# Display_Module.net
KiCad netlist of a schematic drawn in Altium Designer
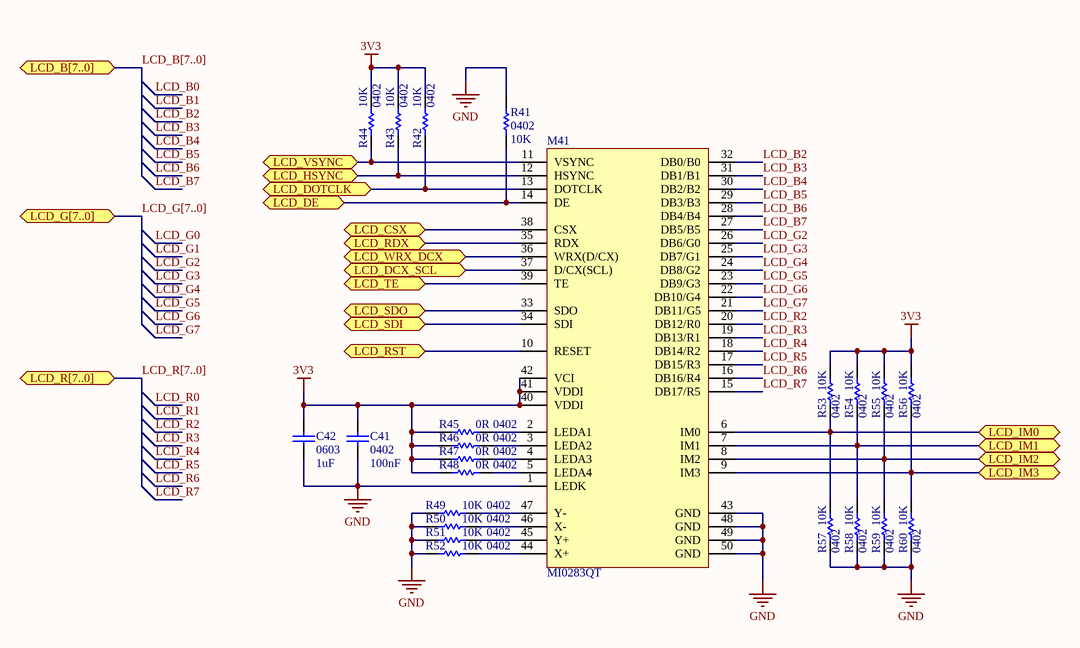
[diagram p0: Display Module.SchDoc]

(export (version "E")
  (design (tool "Eeschema 10.0.6"))
  (components
    (comp (ref "C41")
      (value "0402")
      (footprint "CAPC1005X06N")
      (description "Capacitor")
      (fields (field (name "ALTIUM_VALUE") "100nF") (field (name "PUBLISHER") "Altium Limited"))
      (libsource (lib "Miscellaneous Devices") (part "Cap"))
    )
    (comp (ref "C42")
      (value "0603")
      (footprint "CAPC1608X10N")
      (description "Capacitor")
      (fields (field (name "ALTIUM_VALUE") "1uF") (field (name "PUBLISHER") "Altium Limited"))
      (libsource (lib "Miscellaneous Devices") (part "Cap"))
    )
    (comp (ref "M41")
      (value "MI0283QT")
      (footprint "2.8_SCREEN_MODULE_SKT")
      (libsource (lib "Schematic_Modules_NES") (part "Screen Module"))
    )
    (comp (ref "R41")
      (value "0402")
      (footprint "RESC1005X04N")
      (description "Resistor")
      (fields (field (name "ALTIUM_VALUE") "10K") (field (name "PUBLISHER") "Altium Limited"))
      (libsource (lib "Miscellaneous Devices") (part "Res1"))
    )
    (comp (ref "R42")
      (value "0402")
      (footprint "RESC1005X04N")
      (description "Resistor")
      (fields (field (name "ALTIUM_VALUE") "10K") (field (name "PUBLISHER") "Altium Limited"))
      (libsource (lib "Miscellaneous Devices") (part "Res1"))
    )
    (comp (ref "R43")
      (value "0402")
      (footprint "RESC1005X04N")
      (description "Resistor")
      (fields (field (name "ALTIUM_VALUE") "10K") (field (name "PUBLISHER") "Altium Limited"))
      (libsource (lib "Miscellaneous Devices") (part "Res1"))
    )
    (comp (ref "R44")
      (value "0402")
      (footprint "RESC1005X04N")
      (description "Resistor")
      (fields (field (name "ALTIUM_VALUE") "10K") (field (name "PUBLISHER") "Altium Limited"))
      (libsource (lib "Miscellaneous Devices") (part "Res1"))
    )
    (comp (ref "R45")
      (value "0402")
      (footprint "RESC1005X04N")
      (description "Resistor")
      (fields (field (name "ALTIUM_VALUE") "0R") (field (name "PUBLISHER") "Altium Limited"))
      (libsource (lib "Miscellaneous Devices") (part "Res1"))
    )
    (comp (ref "R46")
      (value "0402")
      (footprint "RESC1005X04N")
      (description "Resistor")
      (fields (field (name "ALTIUM_VALUE") "0R") (field (name "PUBLISHER") "Altium Limited"))
      (libsource (lib "Miscellaneous Devices") (part "Res1"))
    )
    (comp (ref "R47")
      (value "0402")
      (footprint "RESC1005X04N")
      (description "Resistor")
      (fields (field (name "ALTIUM_VALUE") "0R") (field (name "PUBLISHER") "Altium Limited"))
      (libsource (lib "Miscellaneous Devices") (part "Res1"))
    )
    (comp (ref "R48")
      (value "0402")
      (footprint "RESC1005X04N")
      (description "Resistor")
      (fields (field (name "ALTIUM_VALUE") "0R") (field (name "PUBLISHER") "Altium Limited"))
      (libsource (lib "Miscellaneous Devices") (part "Res1"))
    )
    (comp (ref "R49")
      (value "0402")
      (footprint "RESC1005X04N")
      (description "Resistor")
      (fields (field (name "ALTIUM_VALUE") "10K") (field (name "PUBLISHER") "Altium Limited"))
      (libsource (lib "Miscellaneous Devices") (part "Res1"))
    )
    (comp (ref "R50")
      (value "0402")
      (footprint "RESC1005X04N")
      (description "Resistor")
      (fields (field (name "ALTIUM_VALUE") "10K") (field (name "PUBLISHER") "Altium Limited"))
      (libsource (lib "Miscellaneous Devices") (part "Res1"))
    )
    (comp (ref "R51")
      (value "0402")
      (footprint "RESC1005X04N")
      (description "Resistor")
      (fields (field (name "ALTIUM_VALUE") "10K") (field (name "PUBLISHER") "Altium Limited"))
      (libsource (lib "Miscellaneous Devices") (part "Res1"))
    )
    (comp (ref "R52")
      (value "0402")
      (footprint "RESC1005X04N")
      (description "Resistor")
      (fields (field (name "ALTIUM_VALUE") "10K") (field (name "PUBLISHER") "Altium Limited"))
      (libsource (lib "Miscellaneous Devices") (part "Res1"))
    )
    (comp (ref "R53")
      (value "0402")
      (footprint "RESC1005X04N")
      (description "Resistor")
      (fields (field (name "ALTIUM_VALUE") "10K") (field (name "PUBLISHER") "Altium Limited"))
      (libsource (lib "Miscellaneous Devices") (part "Res1"))
    )
    (comp (ref "R54")
      (value "0402")
      (footprint "RESC1005X04N")
      (description "Resistor")
      (fields (field (name "ALTIUM_VALUE") "10K") (field (name "PUBLISHER") "Altium Limited"))
      (libsource (lib "Miscellaneous Devices") (part "Res1"))
    )
    (comp (ref "R55")
      (value "0402")
      (footprint "RESC1005X04N")
      (description "Resistor")
      (fields (field (name "ALTIUM_VALUE") "10K") (field (name "PUBLISHER") "Altium Limited"))
      (libsource (lib "Miscellaneous Devices") (part "Res1"))
    )
    (comp (ref "R56")
      (value "0402")
      (footprint "RESC1005X04N")
      (description "Resistor")
      (fields (field (name "ALTIUM_VALUE") "10K") (field (name "PUBLISHER") "Altium Limited"))
      (libsource (lib "Miscellaneous Devices") (part "Res1"))
    )
    (comp (ref "R57")
      (value "0402")
      (footprint "RESC1005X04N")
      (description "Resistor")
      (fields (field (name "ALTIUM_VALUE") "10K") (field (name "PUBLISHER") "Altium Limited"))
      (libsource (lib "Miscellaneous Devices") (part "Res1"))
    )
    (comp (ref "R58")
      (value "0402")
      (footprint "RESC1005X04N")
      (description "Resistor")
      (fields (field (name "ALTIUM_VALUE") "10K") (field (name "PUBLISHER") "Altium Limited"))
      (libsource (lib "Miscellaneous Devices") (part "Res1"))
    )
    (comp (ref "R59")
      (value "0402")
      (footprint "RESC1005X04N")
      (description "Resistor")
      (fields (field (name "ALTIUM_VALUE") "10K") (field (name "PUBLISHER") "Altium Limited"))
      (libsource (lib "Miscellaneous Devices") (part "Res1"))
    )
    (comp (ref "R60")
      (value "0402")
      (footprint "RESC1005X04N")
      (description "Resistor")
      (fields (field (name "ALTIUM_VALUE") "10K") (field (name "PUBLISHER") "Altium Limited"))
      (libsource (lib "Miscellaneous Devices") (part "Res1"))
    )
  )
  (nets
    (net (code "3") (name "/LCD_B2") (class "Default")
      (node (ref "M41") (pin "32") (pinfunction "DB0/B0_32") (pintype "passive"))
    )
    (net (code "4") (name "/LCD_B3") (class "Default")
      (node (ref "M41") (pin "31") (pinfunction "DB1/B1_31") (pintype "passive"))
    )
    (net (code "5") (name "/LCD_B4") (class "Default")
      (node (ref "M41") (pin "30") (pinfunction "DB2/B2_30") (pintype "passive"))
    )
    (net (code "6") (name "/LCD_B5") (class "Default")
      (node (ref "M41") (pin "29") (pinfunction "DB3/B3_29") (pintype "passive"))
    )
    (net (code "7") (name "/LCD_B6") (class "Default")
      (node (ref "M41") (pin "28") (pinfunction "DB4/B4_28") (pintype "passive"))
    )
    (net (code "8") (name "/LCD_B7") (class "Default")
      (node (ref "M41") (pin "27") (pinfunction "DB5/B5_27") (pintype "passive"))
    )
    (net (code "10") (name "/LCD_CSX") (class "Default")
      (node (ref "M41") (pin "38") (pinfunction "CSX_38") (pintype "passive"))
    )
    (net (code "11") (name "/LCD_DCX_SCL") (class "Default")
      (node (ref "M41") (pin "37") (pinfunction "D/CX(SCL)_37") (pintype "passive"))
    )
    (net (code "12") (name "/LCD_DE") (class "Default")
      (node (ref "M41") (pin "14") (pinfunction "DE_14") (pintype "passive"))
      (node (ref "R41") (pin "2") (pinfunction "2_2") (pintype "passive"))
    )
    (net (code "13") (name "/LCD_DOTCLK") (class "Default")
      (node (ref "M41") (pin "13") (pinfunction "DOTCLK_13") (pintype "passive"))
      (node (ref "R42") (pin "2") (pinfunction "2_2") (pintype "passive"))
    )
    (net (code "16") (name "/LCD_G2") (class "Default")
      (node (ref "M41") (pin "26") (pinfunction "DB6/G0_26") (pintype "passive"))
    )
    (net (code "17") (name "/LCD_G3") (class "Default")
      (node (ref "M41") (pin "25") (pinfunction "DB7/G1_25") (pintype "passive"))
    )
    (net (code "18") (name "/LCD_G4") (class "Default")
      (node (ref "M41") (pin "24") (pinfunction "DB8/G2_24") (pintype "passive"))
    )
    (net (code "19") (name "/LCD_G5") (class "Default")
      (node (ref "M41") (pin "23") (pinfunction "DB9/G3_23") (pintype "passive"))
    )
    (net (code "20") (name "/LCD_G6") (class "Default")
      (node (ref "M41") (pin "22") (pinfunction "DB10/G4_22") (pintype "passive"))
    )
    (net (code "21") (name "/LCD_G7") (class "Default")
      (node (ref "M41") (pin "21") (pinfunction "DB11/G5_21") (pintype "passive"))
    )
    (net (code "23") (name "/LCD_HSYNC") (class "Default")
      (node (ref "M41") (pin "12") (pinfunction "HSYNC_12") (pintype "passive"))
      (node (ref "R43") (pin "2") (pinfunction "2_2") (pintype "passive"))
    )
    (net (code "24") (name "/LCD_IM0") (class "Default")
      (node (ref "M41") (pin "6") (pinfunction "IM0_6") (pintype "passive"))
      (node (ref "R53") (pin "2") (pinfunction "2_2") (pintype "passive"))
      (node (ref "R57") (pin "1") (pinfunction "1_1") (pintype "passive"))
    )
    (net (code "25") (name "/LCD_IM1") (class "Default")
      (node (ref "M41") (pin "7") (pinfunction "IM1_7") (pintype "passive"))
      (node (ref "R54") (pin "2") (pinfunction "2_2") (pintype "passive"))
      (node (ref "R58") (pin "1") (pinfunction "1_1") (pintype "passive"))
    )
    (net (code "26") (name "/LCD_IM2") (class "Default")
      (node (ref "M41") (pin "8") (pinfunction "IM2_8") (pintype "passive"))
      (node (ref "R55") (pin "2") (pinfunction "2_2") (pintype "passive"))
      (node (ref "R59") (pin "1") (pinfunction "1_1") (pintype "passive"))
    )
    (net (code "27") (name "/LCD_IM3") (class "Default")
      (node (ref "M41") (pin "9") (pinfunction "IM3_9") (pintype "passive"))
      (node (ref "R56") (pin "2") (pinfunction "2_2") (pintype "passive"))
      (node (ref "R60") (pin "1") (pinfunction "1_1") (pintype "passive"))
    )
    (net (code "30") (name "/LCD_R2") (class "Default")
      (node (ref "M41") (pin "20") (pinfunction "DB12/R0_20") (pintype "passive"))
    )
    (net (code "31") (name "/LCD_R3") (class "Default")
      (node (ref "M41") (pin "19") (pinfunction "DB13/R1_19") (pintype "passive"))
    )
    (net (code "32") (name "/LCD_R4") (class "Default")
      (node (ref "M41") (pin "18") (pinfunction "DB14/R2_18") (pintype "passive"))
    )
    (net (code "33") (name "/LCD_R5") (class "Default")
      (node (ref "M41") (pin "17") (pinfunction "DB15/R3_17") (pintype "passive"))
    )
    (net (code "34") (name "/LCD_R6") (class "Default")
      (node (ref "M41") (pin "16") (pinfunction "DB16/R4_16") (pintype "passive"))
    )
    (net (code "35") (name "/LCD_R7") (class "Default")
      (node (ref "M41") (pin "15") (pinfunction "DB17/R5_15") (pintype "passive"))
    )
    (net (code "36") (name "/LCD_RDX") (class "Default")
      (node (ref "M41") (pin "35") (pinfunction "RDX_35") (pintype "passive"))
    )
    (net (code "37") (name "/LCD_RST") (class "Default")
      (node (ref "M41") (pin "10") (pinfunction "RESET_10") (pintype "passive"))
    )
    (net (code "39") (name "/LCD_SDI") (class "Default")
      (node (ref "M41") (pin "34") (pinfunction "SDI_34") (pintype "passive"))
    )
    (net (code "40") (name "/LCD_SDO") (class "Default")
      (node (ref "M41") (pin "33") (pinfunction "SDO_33") (pintype "passive"))
    )
    (net (code "41") (name "/LCD_TE") (class "Default")
      (node (ref "M41") (pin "39") (pinfunction "TE_39") (pintype "passive"))
    )
    (net (code "42") (name "/LCD_VSYNC") (class "Default")
      (node (ref "M41") (pin "11") (pinfunction "VSYNC_11") (pintype "passive"))
      (node (ref "R44") (pin "2") (pinfunction "2_2") (pintype "passive"))
    )
    (net (code "43") (name "/LCD_WRX_DCX") (class "Default")
      (node (ref "M41") (pin "36") (pinfunction "WRX(D/CX)_36") (pintype "passive"))
    )
    (net (code "44") (name "3V3") (class "Default")
      (node (ref "C41") (pin "2") (pinfunction "2_2") (pintype "passive"))
      (node (ref "C42") (pin "2") (pinfunction "2_2") (pintype "passive"))
      (node (ref "M41") (pin "40") (pinfunction "VDDI_40") (pintype "passive"))
      (node (ref "M41") (pin "41") (pinfunction "VDDI_41") (pintype "passive"))
      (node (ref "M41") (pin "42") (pinfunction "VCI_42") (pintype "passive"))
      (node (ref "R42") (pin "1") (pinfunction "1_1") (pintype "passive"))
      (node (ref "R43") (pin "1") (pinfunction "1_1") (pintype "passive"))
      (node (ref "R44") (pin "1") (pinfunction "1_1") (pintype "passive"))
      (node (ref "R45") (pin "2") (pinfunction "2_2") (pintype "passive"))
      (node (ref "R46") (pin "2") (pinfunction "2_2") (pintype "passive"))
      (node (ref "R47") (pin "2") (pinfunction "2_2") (pintype "passive"))
      (node (ref "R48") (pin "2") (pinfunction "2_2") (pintype "passive"))
      (node (ref "R53") (pin "1") (pinfunction "1_1") (pintype "passive"))
      (node (ref "R54") (pin "1") (pinfunction "1_1") (pintype "passive"))
      (node (ref "R55") (pin "1") (pinfunction "1_1") (pintype "passive"))
      (node (ref "R56") (pin "1") (pinfunction "1_1") (pintype "passive"))
    )
    (net (code "45") (name "GND") (class "Default")
      (node (ref "C41") (pin "1") (pinfunction "1_1") (pintype "passive"))
      (node (ref "C42") (pin "1") (pinfunction "1_1") (pintype "passive"))
      (node (ref "M41") (pin "1") (pinfunction "LEDK_1") (pintype "passive"))
      (node (ref "M41") (pin "43") (pinfunction "GND_43") (pintype "passive"))
      (node (ref "M41") (pin "48") (pinfunction "GND_48") (pintype "passive"))
      (node (ref "M41") (pin "49") (pinfunction "GND_49") (pintype "passive"))
      (node (ref "M41") (pin "50") (pinfunction "GND_50") (pintype "passive"))
      (node (ref "R41") (pin "1") (pinfunction "1_1") (pintype "passive"))
      (node (ref "R49") (pin "2") (pinfunction "2_2") (pintype "passive"))
      (node (ref "R50") (pin "2") (pinfunction "2_2") (pintype "passive"))
      (node (ref "R51") (pin "2") (pinfunction "2_2") (pintype "passive"))
      (node (ref "R52") (pin "2") (pinfunction "2_2") (pintype "passive"))
      (node (ref "R57") (pin "2") (pinfunction "2_2") (pintype "passive"))
      (node (ref "R58") (pin "2") (pinfunction "2_2") (pintype "passive"))
      (node (ref "R59") (pin "2") (pinfunction "2_2") (pintype "passive"))
      (node (ref "R60") (pin "2") (pinfunction "2_2") (pintype "passive"))
    )
    (net (code "46") (name "Net-(M41-LEDA1)") (class "Default")
      (node (ref "M41") (pin "2") (pinfunction "LEDA1_2") (pintype "passive"))
      (node (ref "R45") (pin "1") (pinfunction "1_1") (pintype "passive"))
    )
    (net (code "47") (name "Net-(M41-LEDA2)") (class "Default")
      (node (ref "M41") (pin "3") (pinfunction "LEDA2_3") (pintype "passive"))
      (node (ref "R46") (pin "1") (pinfunction "1_1") (pintype "passive"))
    )
    (net (code "48") (name "Net-(M41-LEDA3)") (class "Default")
      (node (ref "M41") (pin "4") (pinfunction "LEDA3_4") (pintype "passive"))
      (node (ref "R47") (pin "1") (pinfunction "1_1") (pintype "passive"))
    )
    (net (code "49") (name "Net-(M41-LEDA4)") (class "Default")
      (node (ref "M41") (pin "5") (pinfunction "LEDA4_5") (pintype "passive"))
      (node (ref "R48") (pin "1") (pinfunction "1_1") (pintype "passive"))
    )
    (net (code "50") (name "Net-(M41-X+)") (class "Default")
      (node (ref "M41") (pin "44") (pinfunction "X+_44") (pintype "passive"))
      (node (ref "R52") (pin "1") (pinfunction "1_1") (pintype "passive"))
    )
    (net (code "51") (name "Net-(M41-X-)") (class "Default")
      (node (ref "M41") (pin "46") (pinfunction "X-_46") (pintype "passive"))
      (node (ref "R50") (pin "1") (pinfunction "1_1") (pintype "passive"))
    )
    (net (code "52") (name "Net-(M41-Y+)") (class "Default")
      (node (ref "M41") (pin "45") (pinfunction "Y+_45") (pintype "passive"))
      (node (ref "R51") (pin "1") (pinfunction "1_1") (pintype "passive"))
    )
    (net (code "53") (name "Net-(M41-Y-)") (class "Default")
      (node (ref "M41") (pin "47") (pinfunction "Y-_47") (pintype "passive"))
      (node (ref "R49") (pin "1") (pinfunction "1_1") (pintype "passive"))
    )
  )
)
